# UTAP2022_SENSOR_v1_1.net
KiCad netlist of a schematic drawn in EAGLE
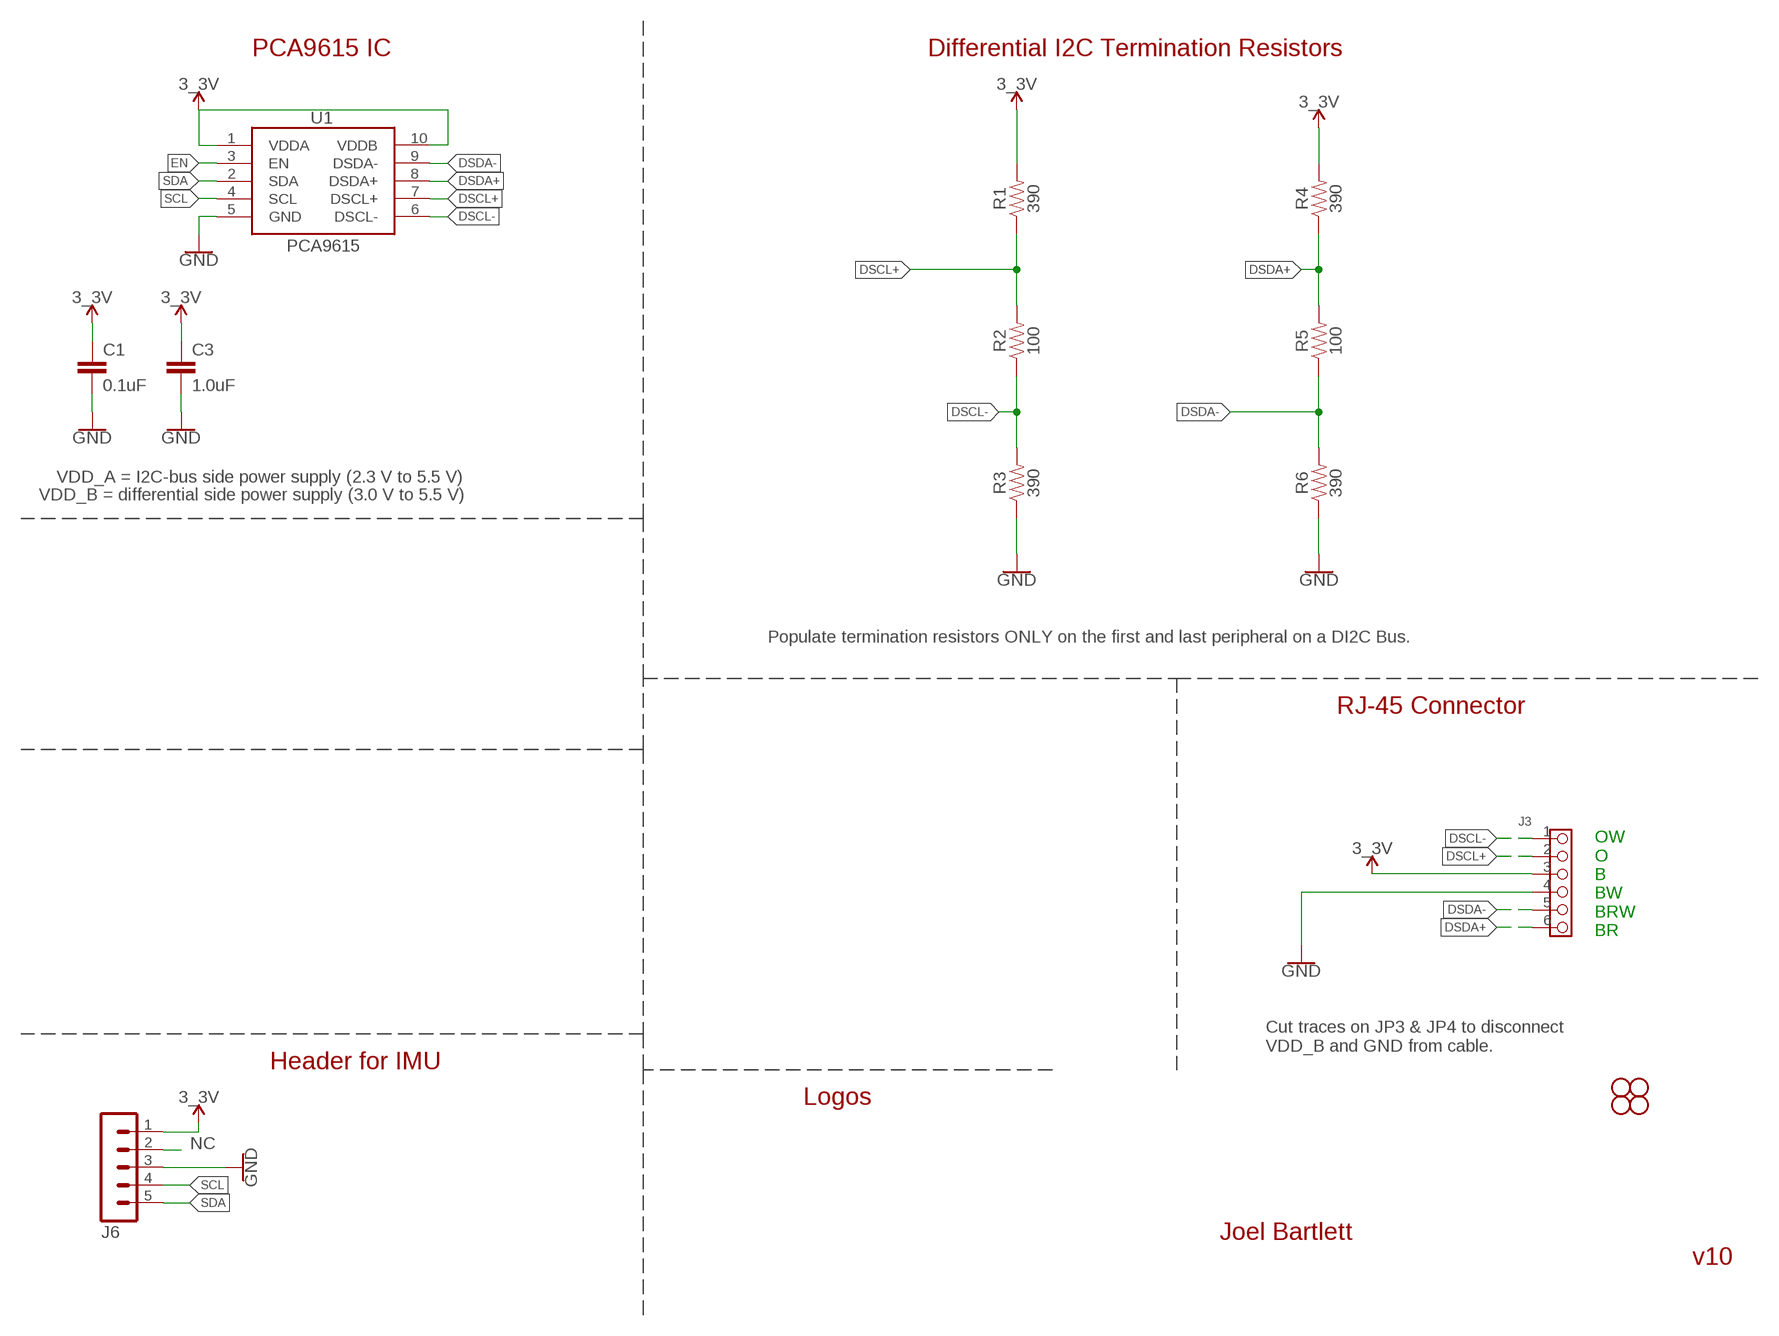
[diagram p0: schematic, sheet 1]

(export (version "E")
  (design (tool "Eeschema 10.0.6"))
  (components
    (comp (ref "C1")
      (value "0.1uF")
      (footprint "eagle-import:0603")
      (libsource (lib "eagle-import") (part "0.1UF-0603-25V-(+80/-20%)"))
    )
    (comp (ref "C3")
      (value "1.0uF")
      (footprint "eagle-import:0603")
      (libsource (lib "eagle-import") (part "1.0UF-0603-16V-10%"))
    )
    (comp (ref "H1")
      (value "STAND-OFF")
      (footprint "eagle-import:STAND-OFF")
      (libsource (lib "eagle-import") (part "STAND-OFF"))
    )
    (comp (ref "H2")
      (value "STAND-OFF")
      (footprint "eagle-import:STAND-OFF")
      (libsource (lib "eagle-import") (part "STAND-OFF"))
    )
    (comp (ref "H3")
      (value "STAND-OFF")
      (footprint "eagle-import:STAND-OFF")
      (libsource (lib "eagle-import") (part "STAND-OFF"))
    )
    (comp (ref "H4")
      (value "STAND-OFF")
      (footprint "eagle-import:STAND-OFF")
      (libsource (lib "eagle-import") (part "STAND-OFF"))
    )
    (comp (ref "J3")
      (value "CONNECTOR_HEADER-6P-55/35MIL")
      (footprint "eagle-import:CONNECTOR_6P-2.54-55_35MIL")
      (libsource (lib "eagle-import") (part "CONNECTOR_HEADER-6P-55/35MIL"))
    )
    (comp (ref "J6")
      (value "MA05-1")
      (footprint "eagle-import:MA05-1")
      (libsource (lib "eagle-import") (part "MA05-1"))
    )
    (comp (ref "R1")
      (value "390")
      (footprint "eagle-import:0603")
      (libsource (lib "eagle-import") (part "390OHM-0603-1/10W-1%"))
    )
    (comp (ref "R2")
      (value "100")
      (footprint "eagle-import:0603")
      (libsource (lib "eagle-import") (part "100OHM-0603-1/10W-1%"))
    )
    (comp (ref "R3")
      (value "390")
      (footprint "eagle-import:0603")
      (libsource (lib "eagle-import") (part "390OHM-0603-1/10W-1%"))
    )
    (comp (ref "R4")
      (value "390")
      (footprint "eagle-import:0603")
      (libsource (lib "eagle-import") (part "390OHM-0603-1/10W-1%"))
    )
    (comp (ref "R5")
      (value "100")
      (footprint "eagle-import:0603")
      (libsource (lib "eagle-import") (part "100OHM-0603-1/10W-1%"))
    )
    (comp (ref "R6")
      (value "390")
      (footprint "eagle-import:0603")
      (libsource (lib "eagle-import") (part "390OHM-0603-1/10W-1%"))
    )
    (comp (ref "U1")
      (value "PCA9615")
      (footprint "eagle-import:TSSOP10")
      (libsource (lib "eagle-import") (part "PCA9615"))
    )
  )
  (nets
    (net (code "1") (name "/NC") (class "Default")
      (node (ref "J6") (pin "2") (pinfunction "2_2") (pintype "passive"))
    )
    (net (code "2") (name "3_3V") (class "Default")
      (node (ref "C1") (pin "1") (pinfunction "1_1") (pintype "passive"))
      (node (ref "C3") (pin "1") (pinfunction "1_1") (pintype "passive"))
      (node (ref "J3") (pin "3") (pinfunction "3_3") (pintype "bidirectional"))
      (node (ref "J6") (pin "1") (pinfunction "1_1") (pintype "passive"))
      (node (ref "R1") (pin "2") (pinfunction "2_2") (pintype "passive"))
      (node (ref "R4") (pin "2") (pinfunction "2_2") (pintype "passive"))
      (node (ref "U1") (pin "1") (pinfunction "VDDA_1") (pintype "bidirectional"))
      (node (ref "U1") (pin "10") (pinfunction "VDDB_10") (pintype "bidirectional"))
    )
    (net (code "3") (name "DSCL+") (class "Default")
      (node (ref "J3") (pin "2") (pinfunction "2_2") (pintype "bidirectional"))
      (node (ref "R1") (pin "1") (pinfunction "1_1") (pintype "passive"))
      (node (ref "R2") (pin "2") (pinfunction "2_2") (pintype "passive"))
      (node (ref "U1") (pin "7") (pinfunction "DSCL+_7") (pintype "bidirectional"))
    )
    (net (code "4") (name "DSCL-") (class "Default")
      (node (ref "J3") (pin "1") (pinfunction "1_1") (pintype "bidirectional"))
      (node (ref "R2") (pin "1") (pinfunction "1_1") (pintype "passive"))
      (node (ref "R3") (pin "2") (pinfunction "2_2") (pintype "passive"))
      (node (ref "U1") (pin "6") (pinfunction "DSCL-_6") (pintype "bidirectional"))
    )
    (net (code "5") (name "DSDA+") (class "Default")
      (node (ref "J3") (pin "6") (pinfunction "6_6") (pintype "bidirectional"))
      (node (ref "R4") (pin "1") (pinfunction "1_1") (pintype "passive"))
      (node (ref "R5") (pin "2") (pinfunction "2_2") (pintype "passive"))
      (node (ref "U1") (pin "8") (pinfunction "DSDA+_8") (pintype "bidirectional"))
    )
    (net (code "6") (name "DSDA-") (class "Default")
      (node (ref "J3") (pin "5") (pinfunction "5_5") (pintype "bidirectional"))
      (node (ref "R5") (pin "1") (pinfunction "1_1") (pintype "passive"))
      (node (ref "R6") (pin "2") (pinfunction "2_2") (pintype "passive"))
      (node (ref "U1") (pin "9") (pinfunction "DSDA-_9") (pintype "bidirectional"))
    )
    (net (code "7") (name "EN") (class "Default")
      (node (ref "U1") (pin "3") (pinfunction "EN_3") (pintype "bidirectional"))
    )
    (net (code "8") (name "GND") (class "Default")
      (node (ref "C1") (pin "2") (pinfunction "2_2") (pintype "passive"))
      (node (ref "C3") (pin "2") (pinfunction "2_2") (pintype "passive"))
      (node (ref "J3") (pin "4") (pinfunction "4_4") (pintype "bidirectional"))
      (node (ref "J6") (pin "3") (pinfunction "3_3") (pintype "passive"))
      (node (ref "R3") (pin "1") (pinfunction "1_1") (pintype "passive"))
      (node (ref "R6") (pin "1") (pinfunction "1_1") (pintype "passive"))
      (node (ref "U1") (pin "5") (pinfunction "GND_5") (pintype "bidirectional"))
    )
    (net (code "9") (name "SCL") (class "Default")
      (node (ref "J6") (pin "4") (pinfunction "4_4") (pintype "passive"))
      (node (ref "U1") (pin "4") (pinfunction "SCL_4") (pintype "bidirectional"))
    )
    (net (code "10") (name "SDA") (class "Default")
      (node (ref "J6") (pin "5") (pinfunction "5_5") (pintype "passive"))
      (node (ref "U1") (pin "2") (pinfunction "SDA_2") (pintype "bidirectional"))
    )
  )
)
